# Speaker.net
KiCad netlist of a schematic drawn in Altium Designer
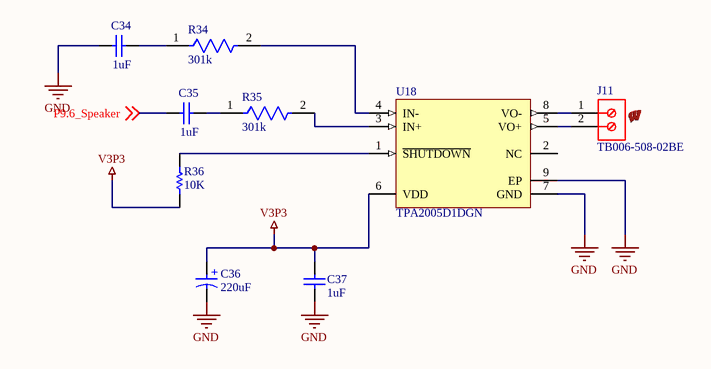
[diagram p0: Speaker.SchDoc]

(export (version "E")
  (design (tool "Eeschema 10.0.6"))
  (components
    (comp (ref "C34")
      (value "1uF")
      (footprint "CAPC2013X145X50NL20T25")
      (fields (field (name "MANUFACTURER") "Kemet") (field (name "PART NUMBER") "C0805S104K5RACTU"))
      (libsource (lib "Altium Content Vault") (part "CAP"))
    )
    (comp (ref "C35")
      (value "1uF")
      (footprint "CAPC2013X145X50NL20T25")
      (fields (field (name "MANUFACTURER") "Kemet") (field (name "PART NUMBER") "C0805S104K5RACTU"))
      (libsource (lib "Altium Content Vault") (part "CAP"))
    )
    (comp (ref "C36")
      (value "220uF")
      (footprint "WCAP-AS5H_D6.3H7.7")
      (description "865230145005 WCAP-AS5H Aluminum Electrolytic Capacitors")
      (libsource (lib "Altium Content Vault") (part "Capacitor_Polarized"))
    )
    (comp (ref "C37")
      (value "1uF")
      (footprint "CAPC2013X145X50NL20T25")
      (fields (field (name "MANUFACTURER") "Kemet") (field (name "PART NUMBER") "C0805S104K5RACTU"))
      (libsource (lib "Altium Content Vault") (part "CAP"))
    )
    (comp (ref "J11")
      (value "CONN_TB006_-508-02BE")
      (footprint "CUI_TB006 -508-02BE")
      (description "2~24 Poles, Screw Type, Horizontal, 5.08 Pitch, 26~14 (AWG), Terminal Block Connector")
      (fields
        (field (name "MF") "CUI Devices")
        (field (name "MP") "TB006 -508-02BE")
        (field (name "MANUFACTURER PART NUMBER") "TB006-508-02BE")
      )
      (libsource (lib "uw-madison-parts") (part "CONN_TB006_-508-02BE"))
    )
    (comp (ref "R34")
      (value "301k")
      (footprint "FP-CRCW1206-Pe3-MFG")
      (description "RES Thick Film, 301kΩ, 1%, 0.25W, 50ppm/°C, 1206")
      (fields (field (name "TOLERANCE") "1%"))
      (libsource (lib "Altium Content Vault") (part "1029c3af85768c4190bb7ad29bc67b5"))
    )
    (comp (ref "R35")
      (value "301k")
      (footprint "FP-CRCW1206-Pe3-MFG")
      (description "RES Thick Film, 301kΩ, 1%, 0.25W, 50ppm/°C, 1206")
      (fields (field (name "TOLERANCE") "1%"))
      (libsource (lib "Altium Content Vault") (part "1029c3af85768c4190bb7ad29bc67b5"))
    )
    (comp (ref "R36")
      (value "10K")
      (footprint "RESC2013X55X40ML15T20")
      (fields (field (name "PART NUMBER") "TNPW0805301KBEEN") (field (name "MANUFACTURER") "Vishay Dale"))
      (libsource (lib "Altium Content Vault") (part "RES"))
    )
    (comp (ref "U18")
      (value "TPA2005D1DGN")
      (footprint "DGN0008D_L")
      (description "1.4-W Mono Class-D Audio Amplifier, -40 to 85 degC, 8-pin SOP (DGN8), Green (RoHS & no Sb/Br)")
      (fields (field (name "MANUFACTURER") "Texas Instruments"))
      (libsource (lib "Altium Content Vault") (part "TI-TPA2005_6D1XDXX8-TP"))
    )
  )
  (nets
    (net (code "1") (name "GND") (class "Default")
      (node (ref "C34") (pin "1") (pinfunction "1_1") (pintype "passive"))
      (node (ref "C36") (pin "2") (pinfunction "N_2") (pintype "passive"))
      (node (ref "C37") (pin "1") (pinfunction "1_1") (pintype "passive"))
      (node (ref "U18") (pin "7") (pinfunction "GND_7") (pintype "power_in"))
      (node (ref "U18") (pin "9") (pinfunction "EP_9") (pintype "power_in"))
    )
    (net (code "2") (name "Net-(C34-Pad2)") (class "Default")
      (node (ref "C34") (pin "2") (pinfunction "2_2") (pintype "passive"))
      (node (ref "R34") (pin "1") (pinfunction "1_1") (pintype "passive"))
    )
    (net (code "3") (name "Net-(C35-Pad2)") (class "Default")
      (node (ref "C35") (pin "2") (pinfunction "2_2") (pintype "passive"))
      (node (ref "R35") (pin "1") (pinfunction "1_1") (pintype "passive"))
    )
    (net (code "4") (name "Net-(U18-IN+)") (class "Default")
      (node (ref "R35") (pin "2") (pinfunction "2_2") (pintype "passive"))
      (node (ref "U18") (pin "3") (pinfunction "IN+_3") (pintype "input"))
    )
    (net (code "5") (name "Net-(U18-IN-)") (class "Default")
      (node (ref "R34") (pin "2") (pinfunction "2_2") (pintype "passive"))
      (node (ref "U18") (pin "4") (pinfunction "IN-_4") (pintype "input"))
    )
    (net (code "6") (name "Net-(U18-VO+)") (class "Default")
      (node (ref "J11") (pin "2") (pinfunction "2_2") (pintype "passive"))
      (node (ref "U18") (pin "5") (pinfunction "VO+_5") (pintype "output"))
    )
    (net (code "7") (name "Net-(U18-VO-)") (class "Default")
      (node (ref "J11") (pin "1") (pinfunction "1_1") (pintype "passive"))
      (node (ref "U18") (pin "8") (pinfunction "VO-_8") (pintype "output"))
    )
    (net (code "8") (name "Net-(U18-~{SHUTDOWN})") (class "Default")
      (node (ref "R36") (pin "2") (pinfunction "2_2") (pintype "passive"))
      (node (ref "U18") (pin "1") (pinfunction "~{SHUTDOWN}_1") (pintype "input"))
    )
    (net (code "9") (name "P9.6_Speaker") (class "Default")
      (node (ref "C35") (pin "1") (pinfunction "1_1") (pintype "passive"))
    )
    (net (code "10") (name "V3P3") (class "Default")
      (node (ref "C36") (pin "1") (pinfunction "P_1") (pintype "passive"))
      (node (ref "C37") (pin "2") (pinfunction "2_2") (pintype "passive"))
      (node (ref "R36") (pin "1") (pinfunction "1_1") (pintype "passive"))
      (node (ref "U18") (pin "6") (pinfunction "VDD_6") (pintype "power_in"))
    )
    (net (code "11") (name "unconnected-(U18-NC-Pad2)") (class "Default")
      (node (ref "U18") (pin "2") (pinfunction "NC_2") (pintype "passive"))
    )
  )
)
